# STLINK1.net
KiCad netlist of a schematic drawn in EasyEDA Pro
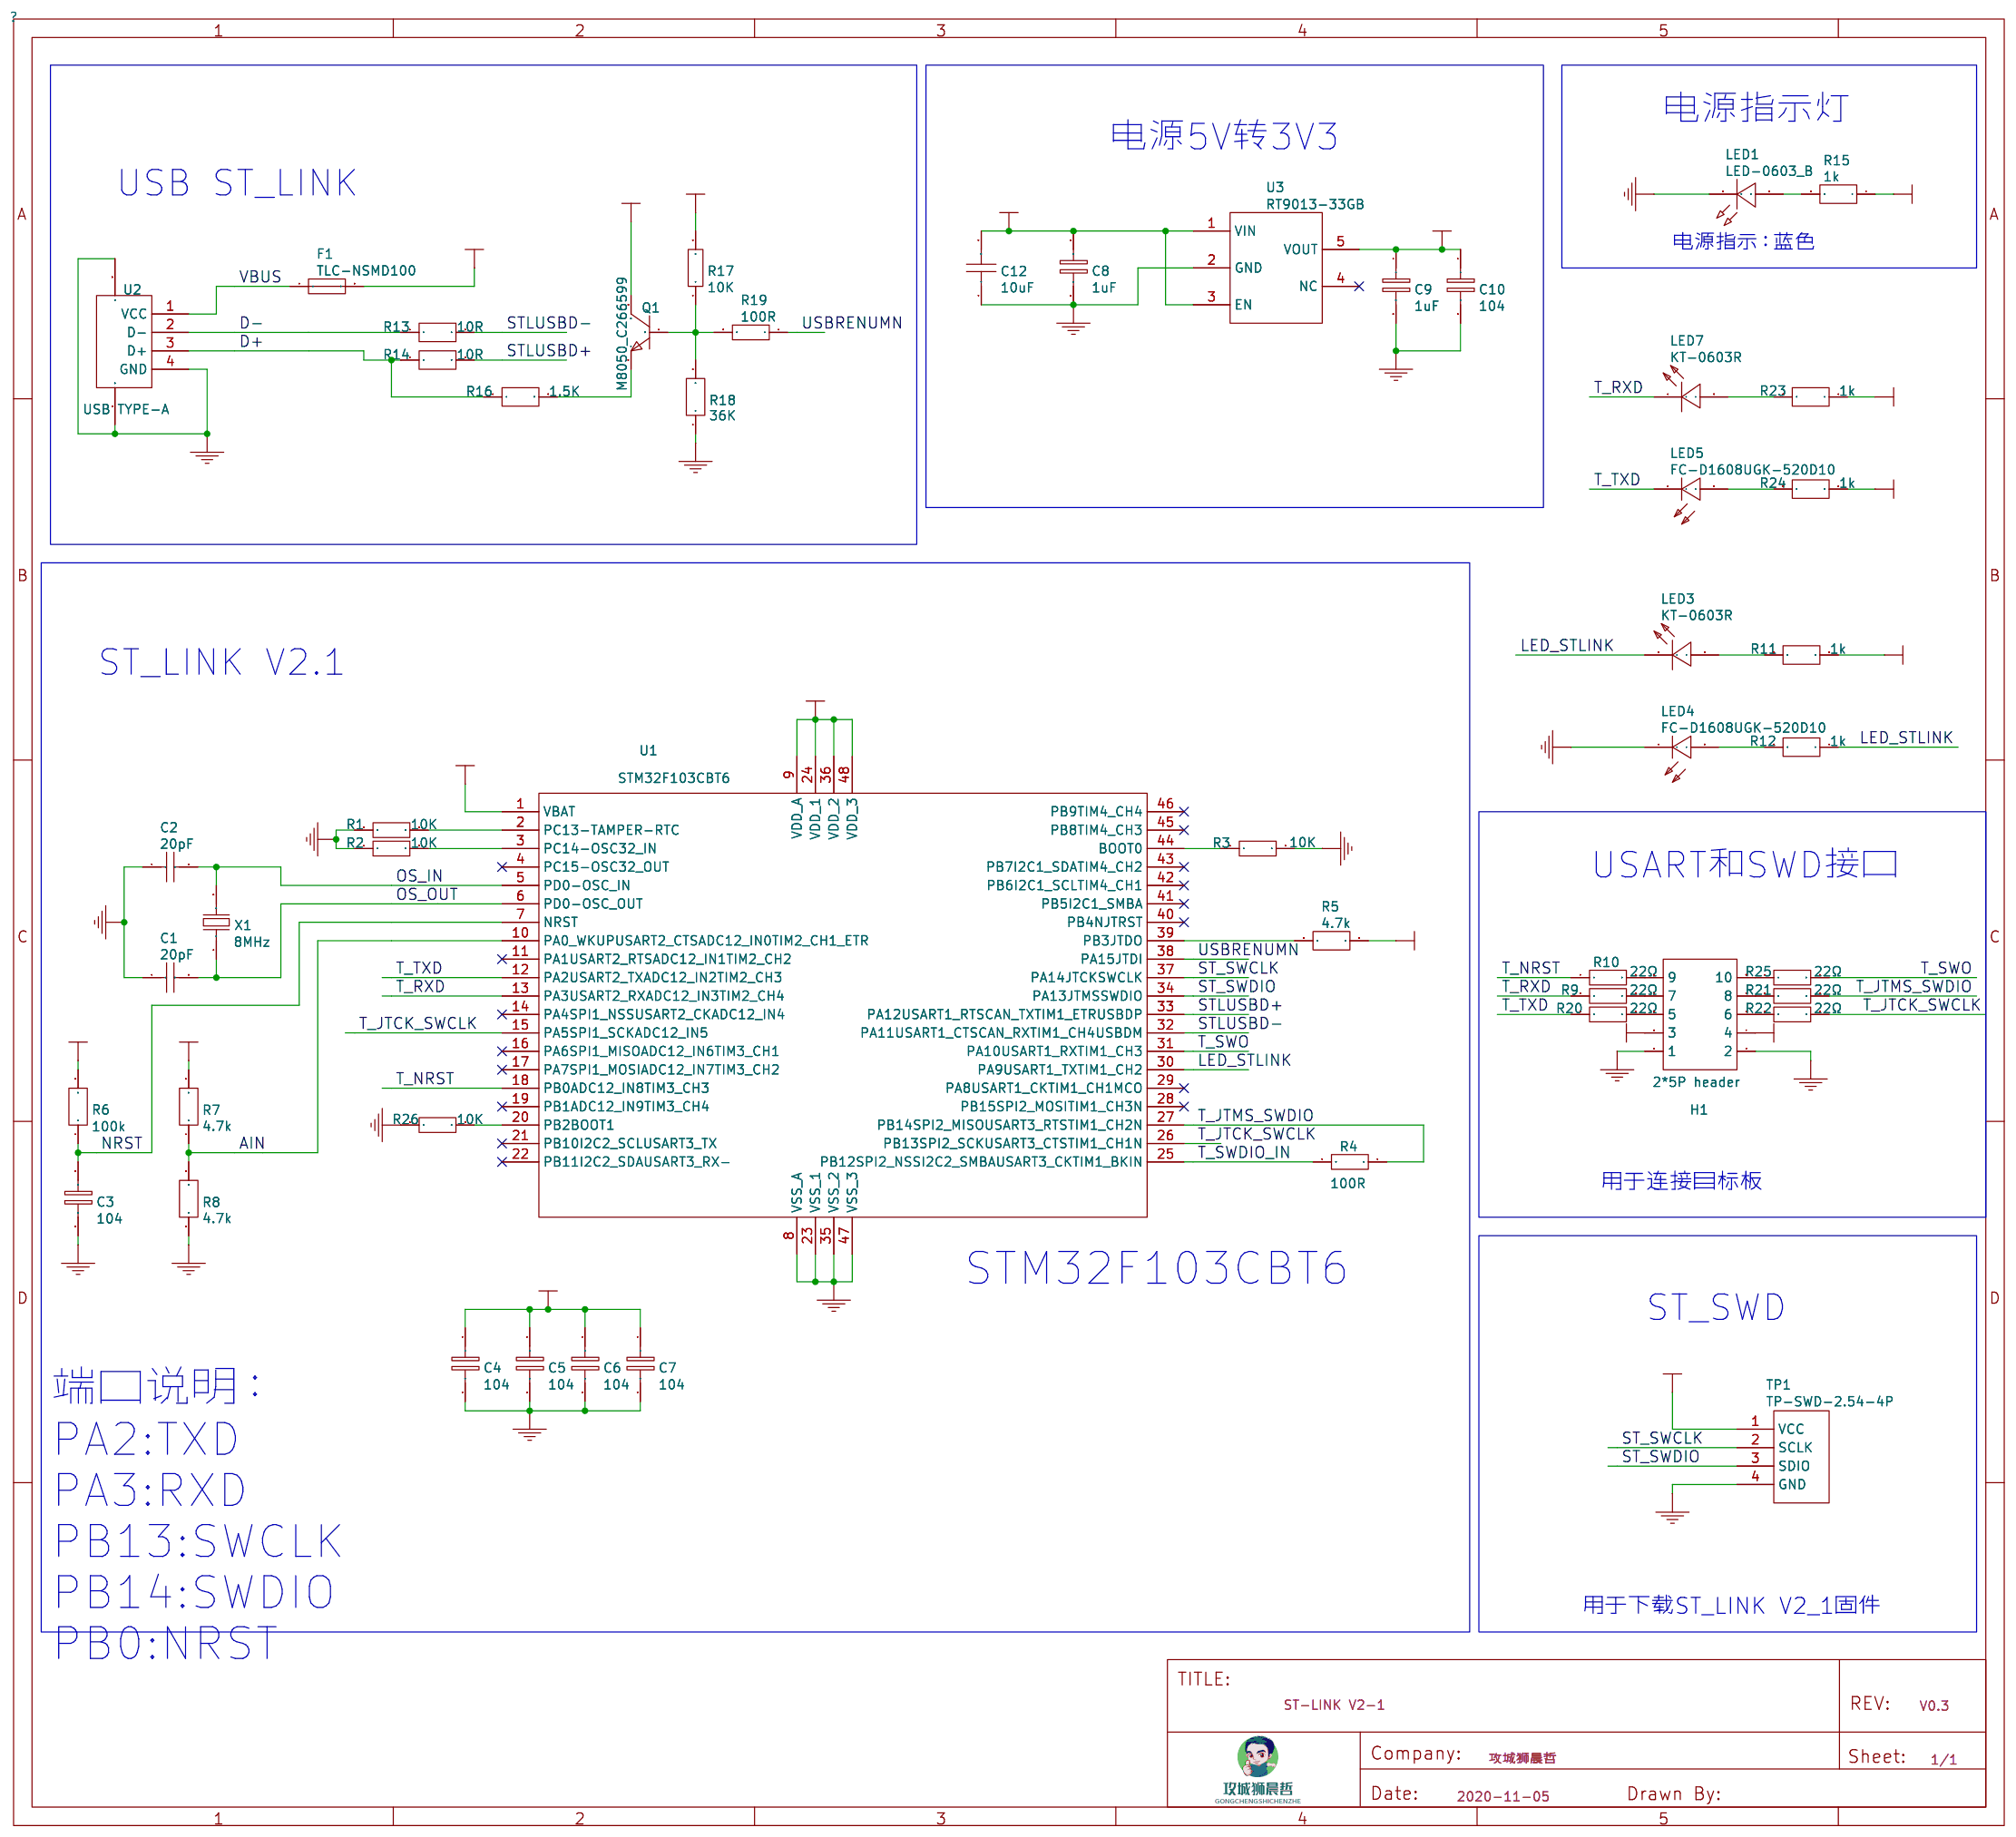
[diagram p0: schematic sheet]

(export (version "E")
  (design (tool "Eeschema 10.0.6"))
  (components
    (comp (ref "C1")
      (value "20pF")
      (footprint "easyedapro:C0603")
      (fields (field (name "Manufacturer Part") "CL10C220JB8NNNC") (field (name "Manufacturer") "SAMSUNG"))
      (libsource (lib "easyedapro") (part "20pF"))
    )
    (comp (ref "C2")
      (value "20pF")
      (footprint "easyedapro:C0603")
      (fields (field (name "Manufacturer Part") "CL10C220JB8NNNC") (field (name "Manufacturer") "SAMSUNG"))
      (libsource (lib "easyedapro") (part "20pF"))
    )
    (comp (ref "C3")
      (value "104")
      (footprint "easyedapro:C0603")
      (fields (field (name "Manufacturer Part") "AC0603KRX7R9BB104") (field (name "Manufacturer") "YAGEO"))
      (libsource (lib "easyedapro") (part "104"))
    )
    (comp (ref "C4")
      (value "104")
      (footprint "easyedapro:C0603")
      (fields (field (name "Manufacturer Part") "AC0603KRX7R9BB104") (field (name "Manufacturer") "YAGEO"))
      (libsource (lib "easyedapro") (part "104"))
    )
    (comp (ref "C5")
      (value "104")
      (footprint "easyedapro:C0603")
      (fields (field (name "Manufacturer Part") "AC0603KRX7R9BB104") (field (name "Manufacturer") "YAGEO"))
      (libsource (lib "easyedapro") (part "104"))
    )
    (comp (ref "C6")
      (value "104")
      (footprint "easyedapro:C0603")
      (fields (field (name "Manufacturer Part") "AC0603KRX7R9BB104") (field (name "Manufacturer") "YAGEO"))
      (libsource (lib "easyedapro") (part "104"))
    )
    (comp (ref "C7")
      (value "104")
      (footprint "easyedapro:C0603")
      (fields (field (name "Manufacturer Part") "AC0603KRX7R9BB104") (field (name "Manufacturer") "YAGEO"))
      (libsource (lib "easyedapro") (part "104"))
    )
    (comp (ref "C8")
      (value "1uF")
      (footprint "easyedapro:C0603")
      (fields (field (name "Manufacturer") "YAGEO"))
      (libsource (lib "easyedapro") (part "1uF"))
    )
    (comp (ref "C9")
      (value "1uF")
      (footprint "easyedapro:C0603")
      (fields (field (name "Manufacturer Part") "CC0603KRX5R8BB105") (field (name "Manufacturer") "YAGEO"))
      (libsource (lib "easyedapro") (part "1uF"))
    )
    (comp (ref "C10")
      (value "104")
      (footprint "easyedapro:C0603")
      (fields (field (name "Manufacturer Part") "AC0603KRX7R9BB104") (field (name "Manufacturer") "YAGEO"))
      (libsource (lib "easyedapro") (part "104"))
    )
    (comp (ref "C12")
      (value "10uF")
      (footprint "easyedapro:C0603")
      (fields
        (field (name "Manufacturer Part") "CL10A106MA8NRNC")
        (field (name "Manufacturer") "SAMSUNG(三星)")
      )
      (libsource (lib "easyedapro") (part "10uF"))
    )
    (comp (ref "F1")
      (value "TLC-NSMD100")
      (footprint "easyedapro:R1206")
      (fields (field (name "Manufacturer") "TLC Electronic"))
      (libsource (lib "easyedapro") (part "TLC-NSMD100"))
    )
    (comp (ref "H1")
      (value "2*5P header")
      (fields (field (name "Manufacturer Part") "MTP125-205R1") (field (name "Manufacturer") "MINTRON"))
      (libsource (lib "easyedapro") (part "2*5P header"))
    )
    (comp (ref "LED1")
      (value "LED-0603_B")
      (footprint "easyedapro:LED0603_BLUE")
      (fields
        (field (name "Manufacturer Part") "19-217/BHC-ZL1M2RY/3T")
        (field (name "Manufacturer") "EVERLIGHT(台湾亿光)")
      )
      (libsource (lib "easyedapro") (part "LED-0603_B"))
    )
    (comp (ref "LED3")
      (value "KT-0603R")
      (footprint "easyedapro:LED0603-RD")
      (fields (field (name "Manufacturer") "KENTO"))
      (libsource (lib "easyedapro") (part "KT-0603R"))
    )
    (comp (ref "LED4")
      (value "FC-D1608UGK-520D10")
      (footprint "easyedapro:LED0603-RD")
      (fields (field (name "Manufacturer Part") "NCD0603G1") (field (name "Manufacturer") "国星光电"))
      (libsource (lib "easyedapro") (part "FC-D1608UGK-520D10"))
    )
    (comp (ref "LED5")
      (value "FC-D1608UGK-520D10")
      (footprint "easyedapro:LED0603-RD")
      (fields (field (name "Manufacturer Part") "NCD0603G1") (field (name "Manufacturer") "国星光电"))
      (libsource (lib "easyedapro") (part "FC-D1608UGK-520D10"))
    )
    (comp (ref "LED7")
      (value "KT-0603R")
      (footprint "easyedapro:LED0603-RD")
      (fields (field (name "Manufacturer") "KENTO"))
      (libsource (lib "easyedapro") (part "KT-0603R"))
    )
    (comp (ref "Q1")
      (value "M8050_C266599")
      (fields
        (field (name "Manufacturer Part") "M8050")
        (field (name "Manufacturer") "Bourne Semicon (Shenzhen)")
      )
      (libsource (lib "easyedapro") (part "M8050_C266599"))
    )
    (comp (ref "R1")
      (value "10K")
      (footprint "easyedapro:R0603")
      (fields (field (name "Manufacturer Part") "AC0603FR-0710KL") (field (name "Manufacturer") "YAGEO"))
      (libsource (lib "easyedapro") (part "10K"))
    )
    (comp (ref "R2")
      (value "10K")
      (footprint "easyedapro:R0603")
      (fields (field (name "Manufacturer Part") "AC0603FR-0710KL") (field (name "Manufacturer") "YAGEO"))
      (libsource (lib "easyedapro") (part "10K"))
    )
    (comp (ref "R3")
      (value "10K")
      (footprint "easyedapro:R0603")
      (fields (field (name "Manufacturer Part") "AC0603FR-0710KL") (field (name "Manufacturer") "YAGEO"))
      (libsource (lib "easyedapro") (part "10K"))
    )
    (comp (ref "R4")
      (value "100R")
      (footprint "easyedapro:R0603")
      (fields (field (name "Manufacturer Part") "RC0603FR-07100RL") (field (name "Manufacturer") "YAGEO"))
      (libsource (lib "easyedapro") (part "100R"))
    )
    (comp (ref "R5")
      (value "4.7k")
      (footprint "easyedapro:R0603")
      (fields (field (name "Manufacturer Part") "AC0603FR-074K7L") (field (name "Manufacturer") "YAGEO"))
      (libsource (lib "") (part "4.7k_1"))
    )
    (comp (ref "R6")
      (value "100k")
      (footprint "easyedapro:R0603")
      (fields (field (name "Manufacturer Part") "AC0603FR-07100KL") (field (name "Manufacturer") "YAGEO"))
      (libsource (lib "easyedapro") (part "100k"))
    )
    (comp (ref "R7")
      (value "4.7k")
      (footprint "easyedapro:R0603")
      (fields (field (name "Manufacturer Part") "AC0603FR-074K7L") (field (name "Manufacturer") "YAGEO"))
      (libsource (lib "easyedapro") (part "4.7k"))
    )
    (comp (ref "R8")
      (value "4.7k")
      (footprint "easyedapro:R0603")
      (fields (field (name "Manufacturer Part") "AC0603FR-074K7L") (field (name "Manufacturer") "YAGEO"))
      (libsource (lib "easyedapro") (part "4.7k"))
    )
    (comp (ref "R9")
      (value "22Ω")
      (footprint "easyedapro:R0603")
      (fields
        (field (name "Manufacturer Part") "0603WAF220JT5E")
        (field (name "Manufacturer") "UNI-ROYAL(厚声)")
      )
      (libsource (lib "easyedapro") (part "22Ω"))
    )
    (comp (ref "R10")
      (value "22Ω")
      (footprint "easyedapro:R0603")
      (fields
        (field (name "Manufacturer Part") "0603WAF220JT5E")
        (field (name "Manufacturer") "UNI-ROYAL(厚声)")
      )
      (libsource (lib "easyedapro") (part "22Ω"))
    )
    (comp (ref "R11")
      (value "1k")
      (footprint "easyedapro:R0603")
      (fields (field (name "Manufacturer Part") "RC0603FR-071KL") (field (name "Manufacturer") "YAGEO"))
      (libsource (lib "easyedapro") (part "1k"))
    )
    (comp (ref "R12")
      (value "1k")
      (footprint "easyedapro:R0603")
      (fields (field (name "Manufacturer Part") "RC0603FR-071KL") (field (name "Manufacturer") "YAGEO"))
      (libsource (lib "easyedapro") (part "1k"))
    )
    (comp (ref "R13")
      (value "10R")
      (footprint "easyedapro:R0603")
      (fields (field (name "Manufacturer Part") "RC0603FR-0710RL") (field (name "Manufacturer") "YAGEO"))
      (libsource (lib "easyedapro") (part "10R"))
    )
    (comp (ref "R14")
      (value "10R")
      (footprint "easyedapro:R0603")
      (fields (field (name "Manufacturer Part") "RC0603FR-0710RL") (field (name "Manufacturer") "YAGEO"))
      (libsource (lib "easyedapro") (part "10R"))
    )
    (comp (ref "R15")
      (value "1k")
      (footprint "easyedapro:R0603")
      (fields (field (name "Manufacturer Part") "RC0603FR-071KL") (field (name "Manufacturer") "YAGEO"))
      (libsource (lib "easyedapro") (part "1k"))
    )
    (comp (ref "R16")
      (value "1.5K")
      (footprint "easyedapro:R0603")
      (fields (field (name "Manufacturer Part") "RC0603FR-071K5L") (field (name "Manufacturer") "YAGEO"))
      (libsource (lib "easyedapro") (part "1.5K"))
    )
    (comp (ref "R17")
      (value "10K")
      (footprint "easyedapro:R0603")
      (fields (field (name "Manufacturer Part") "AC0603FR-0710KL") (field (name "Manufacturer") "YAGEO"))
      (libsource (lib "") (part "10K_1"))
    )
    (comp (ref "R18")
      (value "36K")
      (footprint "easyedapro:R0603")
      (fields (field (name "Manufacturer Part") "AC0603FR-0736KL") (field (name "Manufacturer") "YAGEO"))
      (libsource (lib "easyedapro") (part "36K"))
    )
    (comp (ref "R19")
      (value "100R")
      (footprint "easyedapro:R0603")
      (fields (field (name "Manufacturer Part") "RC0603FR-07100RL") (field (name "Manufacturer") "YAGEO"))
      (libsource (lib "easyedapro") (part "100R"))
    )
    (comp (ref "R20")
      (value "22Ω")
      (footprint "easyedapro:R0603")
      (fields
        (field (name "Manufacturer Part") "0603WAF220JT5E")
        (field (name "Manufacturer") "UNI-ROYAL(厚声)")
      )
      (libsource (lib "easyedapro") (part "22Ω"))
    )
    (comp (ref "R21")
      (value "22Ω")
      (footprint "easyedapro:R0603")
      (fields
        (field (name "Manufacturer Part") "0603WAF220JT5E")
        (field (name "Manufacturer") "UNI-ROYAL(厚声)")
      )
      (libsource (lib "easyedapro") (part "22Ω"))
    )
    (comp (ref "R22")
      (value "22Ω")
      (footprint "easyedapro:R0603")
      (fields
        (field (name "Manufacturer Part") "0603WAF220JT5E")
        (field (name "Manufacturer") "UNI-ROYAL(厚声)")
      )
      (libsource (lib "easyedapro") (part "22Ω"))
    )
    (comp (ref "R23")
      (value "1k")
      (footprint "easyedapro:R0603")
      (fields (field (name "Manufacturer Part") "RC0603FR-071KL") (field (name "Manufacturer") "YAGEO"))
      (libsource (lib "easyedapro") (part "1k"))
    )
    (comp (ref "R24")
      (value "1k")
      (footprint "easyedapro:R0603")
      (fields (field (name "Manufacturer Part") "RC0603FR-071KL") (field (name "Manufacturer") "YAGEO"))
      (libsource (lib "easyedapro") (part "1k"))
    )
    (comp (ref "R25")
      (value "22Ω")
      (footprint "easyedapro:R0603")
      (fields
        (field (name "Manufacturer Part") "0603WAF220JT5E")
        (field (name "Manufacturer") "UNI-ROYAL(厚声)")
      )
      (libsource (lib "easyedapro") (part "22Ω"))
    )
    (comp (ref "R26")
      (value "10K")
      (footprint "easyedapro:R0603")
      (fields (field (name "Manufacturer Part") "AC0603FR-0710KL") (field (name "Manufacturer") "YAGEO"))
      (libsource (lib "easyedapro") (part "10K"))
    )
    (comp (ref "TP1") (value "TP-SWD-2.54-4P") (libsource (lib "easyedapro") (part "TP-SWD-2.54-4P")))
    (comp (ref "U1")
      (value "STM32F103CBT6")
      (fields (field (name "Manufacturer") "STMicroelectronics"))
      (libsource (lib "easyedapro") (part "STM32F103CBT6"))
    )
    (comp (ref "U2")
      (value "USB TYPE-A")
      (fields (field (name "Manufacturer Part") "USB-05") (field (name "Manufacturer") "SOFNG"))
      (libsource (lib "easyedapro") (part "USB TYPE-A"))
    )
    (comp (ref "U3")
      (value "RT9013-33GB")
      (footprint "easyedapro:SOT-23-5_L3.0-W1.7-P0.95-LS2.8-BR")
      (fields (field (name "Manufacturer") "RICHTEK"))
      (libsource (lib "easyedapro") (part "RT9013-33GB"))
    )
    (comp (ref "X1")
      (value "8MHz")
      (footprint "easyedapro:OSC-SMD_L5.0-W3.2")
      (fields (field (name "Manufacturer Part") "7A0808LCSC-AHK2G") (field (name "Manufacturer") "TXC"))
      (libsource (lib "easyedapro") (part "8MHz"))
    )
  )
  (nets
    (net (code "1") (name "+5V") (class "Default")
      (node (ref "C12") (pin "2") (pinfunction "2_2") (pintype "unspecified"))
      (node (ref "C8") (pin "1") (pinfunction "1_1") (pintype "unspecified"))
      (node (ref "F1") (pin "2") (pinfunction "2_2") (pintype "unspecified"))
      (node (ref "R17") (pin "2") (pinfunction "2_2") (pintype "input"))
      (node (ref "U3") (pin "1") (pinfunction "VIN_1") (pintype "unspecified"))
      (node (ref "U3") (pin "3") (pinfunction "EN_3") (pintype "unspecified"))
    )
    (net (code "2") (name "/AIN") (class "Default")
      (node (ref "R7") (pin "1") (pinfunction "1_1") (pintype "unspecified"))
      (node (ref "R8") (pin "2") (pinfunction "2_2") (pintype "unspecified"))
      (node (ref "U1") (pin "10") (pinfunction "PA0_WKUPUSART2_CTSADC12_IN0TIM2_CH1_ETR_10") (pintype "input"))
    )
    (net (code "3") (name "/D+") (class "Default")
      (node (ref "R14") (pin "1") (pinfunction "1_1") (pintype "unspecified"))
      (node (ref "R16") (pin "1") (pinfunction "1_1") (pintype "unspecified"))
      (node (ref "U2") (pin "3") (pinfunction "D+_3") (pintype "unspecified"))
    )
    (net (code "4") (name "/D-") (class "Default")
      (node (ref "R13") (pin "1") (pinfunction "1_1") (pintype "unspecified"))
      (node (ref "U2") (pin "2") (pinfunction "D-_2") (pintype "unspecified"))
    )
    (net (code "5") (name "/LED_STLINK") (class "Default")
      (node (ref "LED3") (pin "1") (pinfunction "K_1") (pintype "unspecified"))
      (node (ref "R12") (pin "1") (pinfunction "1_1") (pintype "unspecified"))
      (node (ref "U1") (pin "30") (pinfunction "PA9USART1_TXTIM1_CH2_30") (pintype "input"))
    )
    (net (code "6") (name "/NRST") (class "Default")
      (node (ref "C3") (pin "1") (pinfunction "1_1") (pintype "unspecified"))
      (node (ref "R6") (pin "1") (pinfunction "1_1") (pintype "unspecified"))
      (node (ref "U1") (pin "7") (pinfunction "NRST_7") (pintype "input"))
    )
    (net (code "7") (name "/OS_IN") (class "Default")
      (node (ref "C2") (pin "2") (pinfunction "2_2") (pintype "input"))
      (node (ref "U1") (pin "5") (pinfunction "PD0-OSC_IN_5") (pintype "input"))
      (node (ref "X1") (pin "2") (pinfunction "2_2") (pintype "unspecified"))
    )
    (net (code "8") (name "/OS_OUT") (class "Default")
      (node (ref "C1") (pin "2") (pinfunction "2_2") (pintype "input"))
      (node (ref "U1") (pin "6") (pinfunction "PD0-OSC_OUT_6") (pintype "input"))
      (node (ref "X1") (pin "1") (pinfunction "1_1") (pintype "unspecified"))
    )
    (net (code "9") (name "/STLUSBD+") (class "Default")
      (node (ref "R14") (pin "2") (pinfunction "2_2") (pintype "unspecified"))
      (node (ref "U1") (pin "33") (pinfunction "PA12USART1_RTSCAN_TXTIM1_ETRUSBDP_33") (pintype "input"))
    )
    (net (code "10") (name "/STLUSBD-") (class "Default")
      (node (ref "R13") (pin "2") (pinfunction "2_2") (pintype "unspecified"))
      (node (ref "U1") (pin "32") (pinfunction "PA11USART1_CTSCAN_RXTIM1_CH4USBDM_32") (pintype "input"))
    )
    (net (code "11") (name "/ST_SWCLK") (class "Default")
      (node (ref "TP1") (pin "2") (pinfunction "SCLK_2") (pintype "unspecified"))
      (node (ref "U1") (pin "37") (pinfunction "PA14JTCKSWCLK_37") (pintype "input"))
    )
    (net (code "12") (name "/ST_SWDIO") (class "Default")
      (node (ref "TP1") (pin "3") (pinfunction "SDIO_3") (pintype "unspecified"))
      (node (ref "U1") (pin "34") (pinfunction "PA13JTMSSWDIO_34") (pintype "input"))
    )
    (net (code "13") (name "/T_JTCK_SWCLK") (class "Default")
      (node (ref "R22") (pin "2") (pinfunction "2_2") (pintype "input"))
      (node (ref "U1") (pin "15") (pinfunction "PA5SPI1_SCKADC12_IN5_15") (pintype "input"))
      (node (ref "U1") (pin "26") (pinfunction "PB13SPI2_SCKUSART3_CTSTIM1_CH1N_26") (pintype "input"))
    )
    (net (code "14") (name "/T_JTMS_SWDIO") (class "Default")
      (node (ref "R21") (pin "2") (pinfunction "2_2") (pintype "input"))
      (node (ref "R4") (pin "1") (pinfunction "1_1") (pintype "unspecified"))
      (node (ref "U1") (pin "27") (pinfunction "PB14SPI2_MISOUSART3_RTSTIM1_CH2N_27") (pintype "input"))
    )
    (net (code "15") (name "/T_NRST") (class "Default")
      (node (ref "R10") (pin "1") (pinfunction "1_1") (pintype "input"))
      (node (ref "U1") (pin "18") (pinfunction "PB0ADC12_IN8TIM3_CH3_18") (pintype "input"))
    )
    (net (code "16") (name "/T_RXD") (class "Default")
      (node (ref "LED7") (pin "1") (pinfunction "K_1") (pintype "unspecified"))
      (node (ref "R9") (pin "1") (pinfunction "1_1") (pintype "input"))
      (node (ref "U1") (pin "13") (pinfunction "PA3USART2_RXADC12_IN3TIM2_CH4_13") (pintype "input"))
    )
    (net (code "17") (name "/T_SWDIO_IN") (class "Default")
      (node (ref "R4") (pin "2") (pinfunction "2_2") (pintype "unspecified"))
      (node (ref "U1") (pin "25") (pinfunction "PB12SPI2_NSSI2C2_SMBAUSART3_CKTIM1_BKIN_25") (pintype "input"))
    )
    (net (code "18") (name "/T_SWO") (class "Default")
      (node (ref "R25") (pin "2") (pinfunction "2_2") (pintype "input"))
      (node (ref "U1") (pin "31") (pinfunction "PA10USART1_RXTIM1_CH3_31") (pintype "input"))
    )
    (net (code "19") (name "/T_TXD") (class "Default")
      (node (ref "LED5") (pin "1") (pinfunction "K_1") (pintype "input"))
      (node (ref "R20") (pin "1") (pinfunction "1_1") (pintype "input"))
      (node (ref "U1") (pin "12") (pinfunction "PA2USART2_TXADC12_IN2TIM2_CH3_12") (pintype "input"))
    )
    (net (code "20") (name "/USBRENUMN") (class "Default")
      (node (ref "R19") (pin "1") (pinfunction "1_1") (pintype "unspecified"))
      (node (ref "U1") (pin "38") (pinfunction "PA15JTDI_38") (pintype "input"))
    )
    (net (code "21") (name "/VBUS") (class "Default")
      (node (ref "F1") (pin "1") (pinfunction "1_1") (pintype "unspecified"))
      (node (ref "U2") (pin "1") (pinfunction "VCC_1") (pintype "unspecified"))
    )
    (net (code "22") (name "3V3") (class "Default")
      (node (ref "C10") (pin "1") (pinfunction "1_1") (pintype "unspecified"))
      (node (ref "C4") (pin "1") (pinfunction "1_1") (pintype "unspecified"))
      (node (ref "C5") (pin "1") (pinfunction "1_1") (pintype "unspecified"))
      (node (ref "C6") (pin "1") (pinfunction "1_1") (pintype "unspecified"))
      (node (ref "C7") (pin "1") (pinfunction "1_1") (pintype "unspecified"))
      (node (ref "C9") (pin "1") (pinfunction "1_1") (pintype "unspecified"))
      (node (ref "H1") (pin "3") (pinfunction "3_3") (pintype "input"))
      (node (ref "H1") (pin "4") (pinfunction "4_4") (pintype "input"))
      (node (ref "Q1") (pin "3") (pinfunction "C_3") (pintype "unspecified"))
      (node (ref "R11") (pin "1") (pinfunction "1_1") (pintype "unspecified"))
      (node (ref "R15") (pin "1") (pinfunction "1_1") (pintype "unspecified"))
      (node (ref "R23") (pin "1") (pinfunction "1_1") (pintype "unspecified"))
      (node (ref "R24") (pin "1") (pinfunction "1_1") (pintype "unspecified"))
      (node (ref "R5") (pin "1") (pinfunction "1_1") (pintype "unspecified"))
      (node (ref "R6") (pin "2") (pinfunction "2_2") (pintype "unspecified"))
      (node (ref "R7") (pin "2") (pinfunction "2_2") (pintype "unspecified"))
      (node (ref "TP1") (pin "1") (pinfunction "VCC_1") (pintype "unspecified"))
      (node (ref "U1") (pin "1") (pinfunction "VBAT_1") (pintype "input"))
      (node (ref "U1") (pin "24") (pinfunction "VDD_1_24") (pintype "input"))
      (node (ref "U1") (pin "36") (pinfunction "VDD_2_36") (pintype "input"))
      (node (ref "U1") (pin "48") (pinfunction "VDD_3_48") (pintype "input"))
      (node (ref "U1") (pin "9") (pinfunction "VDD_A_9") (pintype "input"))
      (node (ref "U3") (pin "5") (pinfunction "VOUT_5") (pintype "unspecified"))
    )
    (net (code "23") (name "GND") (class "Default")
      (node (ref "C1") (pin "1") (pinfunction "1_1") (pintype "input"))
      (node (ref "C10") (pin "2") (pinfunction "2_2") (pintype "unspecified"))
      (node (ref "C12") (pin "1") (pinfunction "1_1") (pintype "unspecified"))
      (node (ref "C2") (pin "1") (pinfunction "1_1") (pintype "input"))
      (node (ref "C3") (pin "2") (pinfunction "2_2") (pintype "unspecified"))
      (node (ref "C4") (pin "2") (pinfunction "2_2") (pintype "unspecified"))
      (node (ref "C5") (pin "2") (pinfunction "2_2") (pintype "unspecified"))
      (node (ref "C6") (pin "2") (pinfunction "2_2") (pintype "unspecified"))
      (node (ref "C7") (pin "2") (pinfunction "2_2") (pintype "unspecified"))
      (node (ref "C8") (pin "2") (pinfunction "2_2") (pintype "unspecified"))
      (node (ref "C9") (pin "2") (pinfunction "2_2") (pintype "unspecified"))
      (node (ref "H1") (pin "1") (pinfunction "1_1") (pintype "input"))
      (node (ref "H1") (pin "2") (pinfunction "2_2") (pintype "input"))
      (node (ref "LED1") (pin "2") (pinfunction "2_2") (pintype "unspecified"))
      (node (ref "LED4") (pin "1") (pinfunction "K_1") (pintype "input"))
      (node (ref "R1") (pin "1") (pinfunction "1_1") (pintype "input"))
      (node (ref "R18") (pin "1") (pinfunction "1_1") (pintype "unspecified"))
      (node (ref "R2") (pin "1") (pinfunction "1_1") (pintype "input"))
      (node (ref "R26") (pin "1") (pinfunction "1_1") (pintype "input"))
      (node (ref "R3") (pin "2") (pinfunction "2_2") (pintype "input"))
      (node (ref "R8") (pin "1") (pinfunction "1_1") (pintype "unspecified"))
      (node (ref "TP1") (pin "4") (pinfunction "GND_4") (pintype "unspecified"))
      (node (ref "U1") (pin "23") (pinfunction "VSS_1_23") (pintype "input"))
      (node (ref "U1") (pin "35") (pinfunction "VSS_2_35") (pintype "input"))
      (node (ref "U1") (pin "47") (pinfunction "VSS_3_47") (pintype "input"))
      (node (ref "U1") (pin "8") (pinfunction "VSS_A_8") (pintype "input"))
      (node (ref "U2") (pin "4") (pinfunction "GND_4") (pintype "unspecified"))
      (node (ref "U2") (pin "5") (pinfunction "5_5") (pintype "unspecified"))
      (node (ref "U2") (pin "6") (pinfunction "6_6") (pintype "unspecified"))
      (node (ref "U3") (pin "2") (pinfunction "GND_2") (pintype "unspecified"))
    )
    (net (code "24") (name "Net-(H1-Pad5)") (class "Default")
      (node (ref "H1") (pin "5") (pinfunction "5_5") (pintype "input"))
      (node (ref "R20") (pin "2") (pinfunction "2_2") (pintype "input"))
    )
    (net (code "25") (name "Net-(H1-Pad6)") (class "Default")
      (node (ref "H1") (pin "6") (pinfunction "6_6") (pintype "input"))
      (node (ref "R22") (pin "1") (pinfunction "1_1") (pintype "input"))
    )
    (net (code "26") (name "Net-(H1-Pad7)") (class "Default")
      (node (ref "H1") (pin "7") (pinfunction "7_7") (pintype "input"))
      (node (ref "R9") (pin "2") (pinfunction "2_2") (pintype "input"))
    )
    (net (code "27") (name "Net-(H1-Pad8)") (class "Default")
      (node (ref "H1") (pin "8") (pinfunction "8_8") (pintype "input"))
      (node (ref "R21") (pin "1") (pinfunction "1_1") (pintype "input"))
    )
    (net (code "28") (name "Net-(H1-Pad9)") (class "Default")
      (node (ref "H1") (pin "9") (pinfunction "9_9") (pintype "input"))
      (node (ref "R10") (pin "2") (pinfunction "2_2") (pintype "input"))
    )
    (net (code "29") (name "Net-(H1-Pad10)") (class "Default")
      (node (ref "H1") (pin "10") (pinfunction "10_10") (pintype "input"))
      (node (ref "R25") (pin "1") (pinfunction "1_1") (pintype "input"))
    )
    (net (code "30") (name "Net-(LED1-Pad1)") (class "Default")
      (node (ref "LED1") (pin "1") (pinfunction "1_1") (pintype "unspecified"))
      (node (ref "R15") (pin "2") (pinfunction "2_2") (pintype "unspecified"))
    )
    (net (code "31") (name "Net-(LED3-A)") (class "Default")
      (node (ref "LED3") (pin "2") (pinfunction "A_2") (pintype "unspecified"))
      (node (ref "R11") (pin "2") (pinfunction "2_2") (pintype "unspecified"))
    )
    (net (code "32") (name "Net-(LED4-A)") (class "Default")
      (node (ref "LED4") (pin "2") (pinfunction "A_2") (pintype "input"))
      (node (ref "R12") (pin "2") (pinfunction "2_2") (pintype "unspecified"))
    )
    (net (code "33") (name "Net-(LED5-A)") (class "Default")
      (node (ref "LED5") (pin "2") (pinfunction "A_2") (pintype "input"))
      (node (ref "R24") (pin "2") (pinfunction "2_2") (pintype "unspecified"))
    )
    (net (code "34") (name "Net-(LED7-A)") (class "Default")
      (node (ref "LED7") (pin "2") (pinfunction "A_2") (pintype "unspecified"))
      (node (ref "R23") (pin "2") (pinfunction "2_2") (pintype "unspecified"))
    )
    (net (code "35") (name "Net-(Q1-B)") (class "Default")
      (node (ref "Q1") (pin "1") (pinfunction "B_1") (pintype "unspecified"))
      (node (ref "R17") (pin "1") (pinfunction "1_1") (pintype "input"))
      (node (ref "R18") (pin "2") (pinfunction "2_2") (pintype "unspecified"))
      (node (ref "R19") (pin "2") (pinfunction "2_2") (pintype "unspecified"))
    )
    (net (code "36") (name "Net-(Q1-E)") (class "Default")
      (node (ref "Q1") (pin "2") (pinfunction "E_2") (pintype "unspecified"))
      (node (ref "R16") (pin "2") (pinfunction "2_2") (pintype "unspecified"))
    )
    (net (code "37") (name "Net-(U1-BOOT0)") (class "Default")
      (node (ref "R3") (pin "1") (pinfunction "1_1") (pintype "input"))
      (node (ref "U1") (pin "44") (pinfunction "BOOT0_44") (pintype "input"))
    )
    (net (code "38") (name "Net-(U1-PB2BOOT1)") (class "Default")
      (node (ref "R26") (pin "2") (pinfunction "2_2") (pintype "input"))
      (node (ref "U1") (pin "20") (pinfunction "PB2BOOT1_20") (pintype "input"))
    )
    (net (code "39") (name "Net-(U1-PB3JTDO)") (class "Default")
      (node (ref "R5") (pin "2") (pinfunction "2_2") (pintype "unspecified"))
      (node (ref "U1") (pin "39") (pinfunction "PB3JTDO_39") (pintype "input"))
    )
    (net (code "40") (name "Net-(U1-PC13-TAMPER-RTC)") (class "Default")
      (node (ref "R1") (pin "2") (pinfunction "2_2") (pintype "input"))
      (node (ref "U1") (pin "2") (pinfunction "PC13-TAMPER-RTC_2") (pintype "input"))
    )
    (net (code "41") (name "Net-(U1-PC14-OSC32_IN)") (class "Default")
      (node (ref "R2") (pin "2") (pinfunction "2_2") (pintype "input"))
      (node (ref "U1") (pin "3") (pinfunction "PC14-OSC32_IN_3") (pintype "input"))
    )
    (net (code "42") (name "unconnected-(U1-PA1USART2_RTSADC12_IN1TIM2_CH2-Pad11)") (class "Default")
      (node (ref "U1") (pin "11") (pinfunction "PA1USART2_RTSADC12_IN1TIM2_CH2_11") (pintype "input+no_connect"))
    )
    (net (code "43") (name "unconnected-(U1-PA4SPI1_NSSUSART2_CKADC12_IN4-Pad14)") (class "Default")
      (node (ref "U1") (pin "14") (pinfunction "PA4SPI1_NSSUSART2_CKADC12_IN4_14") (pintype "input+no_connect"))
    )
    (net (code "44") (name "unconnected-(U1-PA6SPI1_MISOADC12_IN6TIM3_CH1-Pad16)") (class "Default")
      (node (ref "U1") (pin "16") (pinfunction "PA6SPI1_MISOADC12_IN6TIM3_CH1_16") (pintype "input+no_connect"))
    )
    (net (code "45") (name "unconnected-(U1-PA7SPI1_MOSIADC12_IN7TIM3_CH2-Pad17)") (class "Default")
      (node (ref "U1") (pin "17") (pinfunction "PA7SPI1_MOSIADC12_IN7TIM3_CH2_17") (pintype "input+no_connect"))
    )
    (net (code "46") (name "unconnected-(U1-PA8USART1_CKTIM1_CH1MCO-Pad29)") (class "Default")
      (node (ref "U1") (pin "29") (pinfunction "PA8USART1_CKTIM1_CH1MCO_29") (pintype "input+no_connect"))
    )
    (net (code "47") (name "unconnected-(U1-PB1ADC12_IN9TIM3_CH4-Pad19)") (class "Default")
      (node (ref "U1") (pin "19") (pinfunction "PB1ADC12_IN9TIM3_CH4_19") (pintype "input+no_connect"))
    )
    (net (code "48") (name "unconnected-(U1-PB4NJTRST-Pad40)") (class "Default")
      (node (ref "U1") (pin "40") (pinfunction "PB4NJTRST_40") (pintype "input+no_connect"))
    )
    (net (code "49") (name "unconnected-(U1-PB5I2C1_SMBA-Pad41)") (class "Default")
      (node (ref "U1") (pin "41") (pinfunction "PB5I2C1_SMBA_41") (pintype "input+no_connect"))
    )
    (net (code "50") (name "unconnected-(U1-PB6I2C1_SCLTIM4_CH1-Pad42)") (class "Default")
      (node (ref "U1") (pin "42") (pinfunction "PB6I2C1_SCLTIM4_CH1_42") (pintype "input+no_connect"))
    )
    (net (code "51") (name "unconnected-(U1-PB7I2C1_SDATIM4_CH2-Pad43)") (class "Default")
      (node (ref "U1") (pin "43") (pinfunction "PB7I2C1_SDATIM4_CH2_43") (pintype "input+no_connect"))
    )
    (net (code "52") (name "unconnected-(U1-PB8TIM4_CH3-Pad45)") (class "Default")
      (node (ref "U1") (pin "45") (pinfunction "PB8TIM4_CH3_45") (pintype "input+no_connect"))
    )
    (net (code "53") (name "unconnected-(U1-PB9TIM4_CH4-Pad46)") (class "Default")
      (node (ref "U1") (pin "46") (pinfunction "PB9TIM4_CH4_46") (pintype "input+no_connect"))
    )
    (net (code "54") (name "unconnected-(U1-PB10I2C2_SCLUSART3_TX-Pad21)") (class "Default")
      (node (ref "U1") (pin "21") (pinfunction "PB10I2C2_SCLUSART3_TX_21") (pintype "input+no_connect"))
    )
    (net (code "55") (name "unconnected-(U1-PB11I2C2_SDAUSART3_RX--Pad22)") (class "Default")
      (node (ref "U1") (pin "22") (pinfunction "PB11I2C2_SDAUSART3_RX-_22") (pintype "input+no_connect"))
    )
    (net (code "56") (name "unconnected-(U1-PB15SPI2_MOSITIM1_CH3N-Pad28)") (class "Default")
      (node (ref "U1") (pin "28") (pinfunction "PB15SPI2_MOSITIM1_CH3N_28") (pintype "input+no_connect"))
    )
    (net (code "57") (name "unconnected-(U1-PC15-OSC32_OUT-Pad4)") (class "Default")
      (node (ref "U1") (pin "4") (pinfunction "PC15-OSC32_OUT_4") (pintype "input+no_connect"))
    )
    (net (code "58") (name "unconnected-(U3-NC-Pad4)") (class "Default")
      (node (ref "U3") (pin "4") (pinfunction "NC_4") (pintype "unspecified+no_connect"))
    )
  )
)
